# STM32F030F4P6.net
KiCad netlist of a schematic drawn in Altium Designer
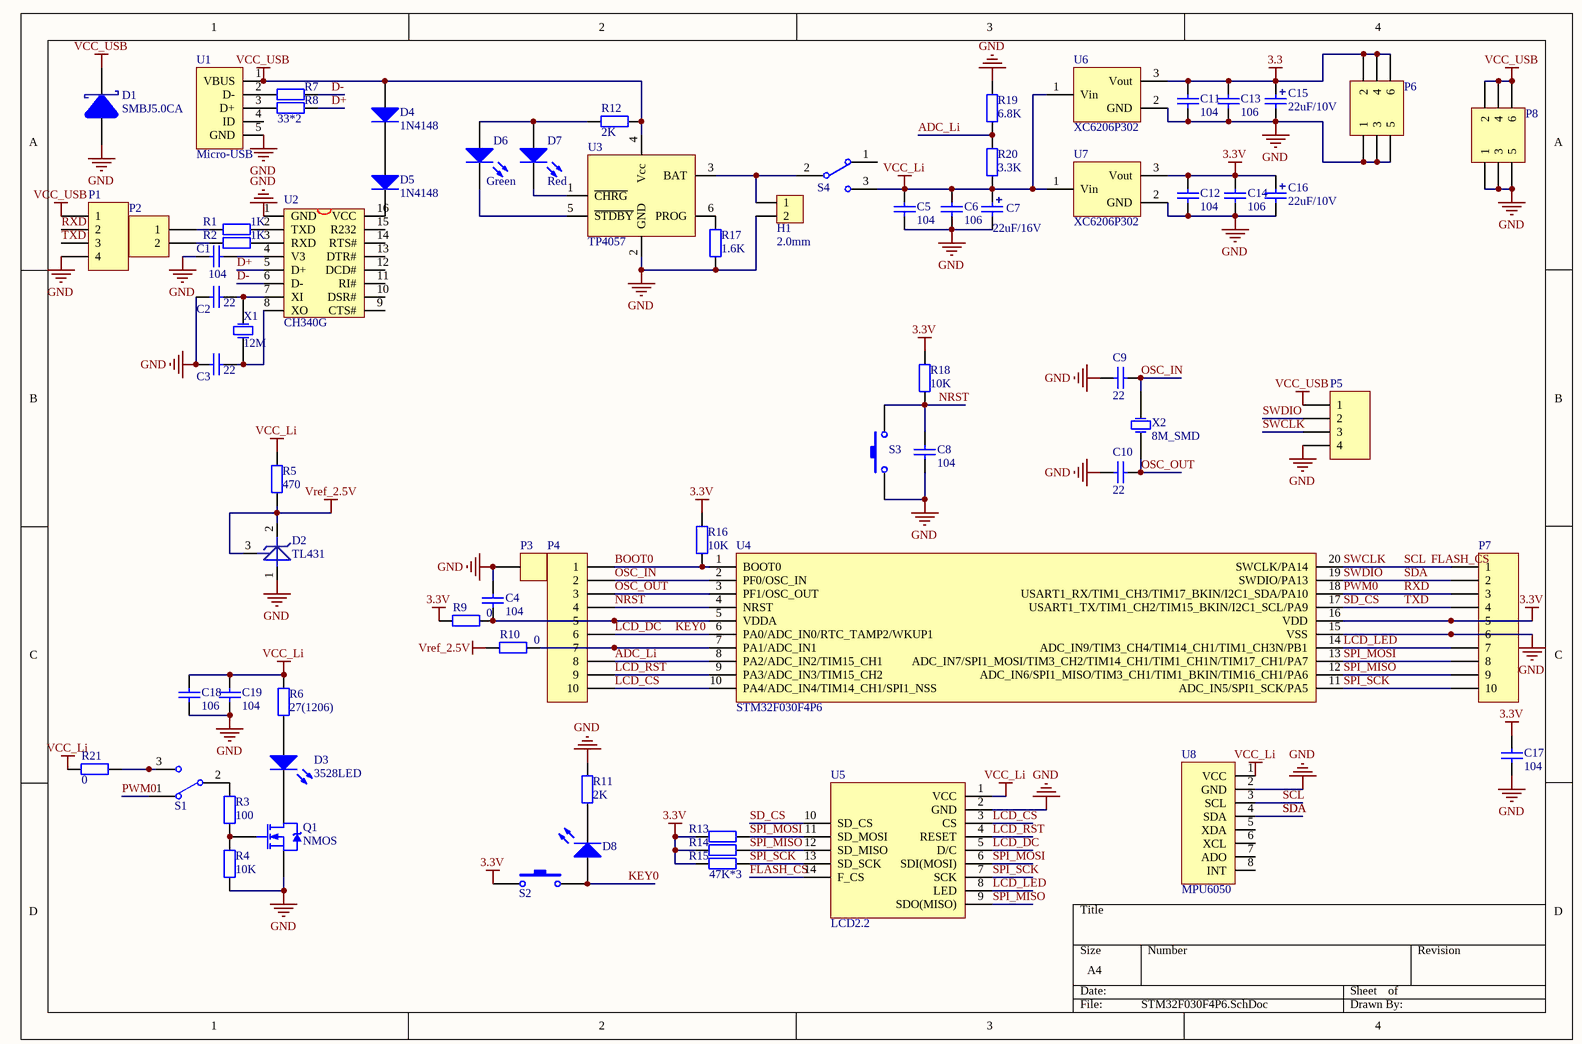
[diagram p0: STM32F030F4P6.SchDoc]

(export (version "E")
  (design (tool "Eeschema 10.0.6"))
  (components
    (comp (ref "C1")
      (value "104")
      (footprint "0603")
      (description "Capacitor")
      (fields (field (name "Comment") "Cap1") (field (name "PUBLISHER") "Altium Limited"))
      (libsource (lib "weifengdq") (part "Cap1"))
    )
    (comp (ref "C2")
      (value "22")
      (footprint "0603")
      (description "Capacitor")
      (fields (field (name "Comment") "Cap1") (field (name "PUBLISHER") "Altium Limited"))
      (libsource (lib "weifengdq") (part "Cap1"))
    )
    (comp (ref "C3")
      (value "22")
      (footprint "0603")
      (description "Capacitor")
      (fields (field (name "Comment") "Cap1") (field (name "PUBLISHER") "Altium Limited"))
      (libsource (lib "weifengdq") (part "Cap1"))
    )
    (comp (ref "C4")
      (value "104")
      (footprint "0603")
      (description "Capacitor")
      (fields (field (name "Comment") "Cap1") (field (name "PUBLISHER") "Altium Limited"))
      (libsource (lib "weifengdq") (part "Cap1"))
    )
    (comp (ref "C5")
      (value "104")
      (footprint "0603")
      (description "Capacitor")
      (fields (field (name "Comment") "Cap1") (field (name "PUBLISHER") "Altium Limited"))
      (libsource (lib "weifengdq") (part "Cap1"))
    )
    (comp (ref "C6")
      (value "106")
      (footprint "0603")
      (description "Capacitor")
      (fields (field (name "Comment") "Cap1") (field (name "PUBLISHER") "Altium Limited"))
      (libsource (lib "weifengdq") (part "Cap1"))
    )
    (comp (ref "C7")
      (value "22uF/16V")
      (footprint "3528(22u16V钽电容)")
      (description "Capacitor")
      (fields (field (name "Comment") "Cap_Pol") (field (name "PUBLISHER") "Altium Limited"))
      (libsource (lib "weifengdq") (part "Cap_Pol"))
    )
    (comp (ref "C8")
      (value "104")
      (footprint "0603")
      (description "Capacitor")
      (fields (field (name "Comment") "Cap1") (field (name "PUBLISHER") "Altium Limited"))
      (libsource (lib "weifengdq") (part "Cap1"))
    )
    (comp (ref "C9")
      (value "22")
      (footprint "0603")
      (description "Capacitor")
      (fields (field (name "Comment") "Cap1") (field (name "PUBLISHER") "Altium Limited"))
      (libsource (lib "weifengdq") (part "Cap1"))
    )
    (comp (ref "C10")
      (value "22")
      (footprint "0603")
      (description "Capacitor")
      (fields (field (name "Comment") "Cap1") (field (name "PUBLISHER") "Altium Limited"))
      (libsource (lib "weifengdq") (part "Cap1"))
    )
    (comp (ref "C11")
      (value "104")
      (footprint "0603")
      (description "Capacitor")
      (fields (field (name "Comment") "Cap1") (field (name "PUBLISHER") "Altium Limited"))
      (libsource (lib "weifengdq") (part "Cap1"))
    )
    (comp (ref "C12")
      (value "104")
      (footprint "0603")
      (description "Capacitor")
      (fields (field (name "Comment") "Cap1") (field (name "PUBLISHER") "Altium Limited"))
      (libsource (lib "weifengdq") (part "Cap1"))
    )
    (comp (ref "C13")
      (value "106")
      (footprint "0603")
      (description "Capacitor")
      (fields (field (name "Comment") "Cap1") (field (name "PUBLISHER") "Altium Limited"))
      (libsource (lib "weifengdq") (part "Cap1"))
    )
    (comp (ref "C14")
      (value "106")
      (footprint "0603")
      (description "Capacitor")
      (fields (field (name "Comment") "Cap1") (field (name "PUBLISHER") "Altium Limited"))
      (libsource (lib "weifengdq") (part "Cap1"))
    )
    (comp (ref "C15")
      (value "22uF/10V")
      (footprint "3216[1206]")
      (description "Capacitor")
      (fields (field (name "Comment") "Cap_Pol") (field (name "PUBLISHER") "Altium Limited"))
      (libsource (lib "weifengdq") (part "Cap_Pol"))
    )
    (comp (ref "C16")
      (value "22uF/10V")
      (footprint "3216[1206]")
      (description "Capacitor")
      (fields (field (name "Comment") "Cap_Pol") (field (name "PUBLISHER") "Altium Limited"))
      (libsource (lib "weifengdq") (part "Cap_Pol"))
    )
    (comp (ref "C17")
      (value "104")
      (footprint "0603")
      (description "Capacitor")
      (fields (field (name "Comment") "Cap1") (field (name "PUBLISHER") "Altium Limited"))
      (libsource (lib "weifengdq") (part "Cap1"))
    )
    (comp (ref "C18")
      (value "106")
      (footprint "0603")
      (description "Capacitor")
      (fields (field (name "Comment") "Cap1") (field (name "PUBLISHER") "Altium Limited"))
      (libsource (lib "weifengdq") (part "Cap1"))
    )
    (comp (ref "C19")
      (value "104")
      (footprint "0603")
      (description "Capacitor")
      (fields (field (name "Comment") "Cap1") (field (name "PUBLISHER") "Altium Limited"))
      (libsource (lib "weifengdq") (part "Cap1"))
    )
    (comp (ref "D1") (value "SMBJ5.0CA") (footprint "TVS") (libsource (lib "weifengdq") (part "TVS")))
    (comp (ref "D2") (value "TL431") (footprint "SOT-23") (libsource (lib "weifengdq") (part "TL431-SOT23")))
    (comp (ref "D3")
      (value "3528LED")
      (footprint "3528(22u16V钽电容)")
      (description "Typical INFRARED GaAs LED")
      (fields (field (name "PUBLISHER") "Altium Limited"))
      (libsource (lib "weifengdq") (part "LED1"))
    )
    (comp (ref "D4")
      (value "1N4148")
      (footprint "1N4148")
      (description "Default Diode")
      (fields (field (name "PUBLISHER") "Altium Limited"))
      (libsource (lib "weifengdq") (part "1N4148"))
    )
    (comp (ref "D5")
      (value "1N4148")
      (footprint "1N4148")
      (description "Default Diode")
      (fields (field (name "PUBLISHER") "Altium Limited"))
      (libsource (lib "weifengdq") (part "1N4148"))
    )
    (comp (ref "D6")
      (value "Green")
      (footprint "0603-Polar")
      (description "Typical INFRARED GaAs LED")
      (fields (field (name "PUBLISHER") "Altium Limited"))
      (libsource (lib "weifengdq") (part "LED1"))
    )
    (comp (ref "D7")
      (value "Red")
      (footprint "0603-Polar")
      (description "Typical INFRARED GaAs LED")
      (fields (field (name "PUBLISHER") "Altium Limited"))
      (libsource (lib "weifengdq") (part "LED1"))
    )
    (comp (ref "D8")
      (value "LED1")
      (footprint "0603-Polar")
      (description "Typical INFRARED GaAs LED")
      (fields (field (name "PUBLISHER") "Altium Limited"))
      (libsource (lib "weifengdq") (part "LED1"))
    )
    (comp (ref "H1") (value "2.0mm") (footprint "H2-防反 2.0") (libsource (lib "weifengdq") (part "H2-防反")))
    (comp (ref "P1")
      (value "Header 4")
      (footprint "HDR1X4")
      (description "Header, 4-Pin")
      (fields (field (name "PUBLISHER") "Altium Limited"))
      (libsource (lib "Miscellaneous Connectors") (part "Header 4"))
    )
    (comp (ref "P2")
      (value "Header 2")
      (footprint "HDR1X2")
      (description "Header, 2-Pin")
      (fields (field (name "PUBLISHER") "Altium Limited"))
      (libsource (lib "Miscellaneous Connectors") (part "Header 2"))
    )
    (comp (ref "P3") (value "TEST") (footprint "HDR1X1") (libsource (lib "weifengdq") (part "TEST")))
    (comp (ref "P4")
      (value "Header 10")
      (footprint "HDR1X10")
      (description "Header, 10-Pin")
      (fields (field (name "PUBLISHER") "Altium Limited"))
      (libsource (lib "") (part "Header 10_1"))
    )
    (comp (ref "P5")
      (value "Header 4")
      (footprint "HDR1X4")
      (description "Header, 4-Pin")
      (fields (field (name "PUBLISHER") "Altium Limited"))
      (libsource (lib "Miscellaneous Connectors") (part "Header 4"))
    )
    (comp (ref "P6")
      (value "Header 3X2")
      (footprint "HDR2X3")
      (description "Header, 3-Pin, Dual row")
      (fields (field (name "PUBLISHER") "Altium Limited"))
      (libsource (lib "Miscellaneous Connectors") (part "Header 3X2"))
    )
    (comp (ref "P7")
      (value "Header 10")
      (footprint "HDR1X10")
      (description "Header, 10-Pin")
      (fields (field (name "PUBLISHER") "Altium Limited"))
      (libsource (lib "Miscellaneous Connectors") (part "Header 10"))
    )
    (comp (ref "P8")
      (value "Header 3X2")
      (footprint "HDR2X3")
      (description "Header, 3-Pin, Dual row")
      (fields (field (name "PUBLISHER") "Altium Limited"))
      (libsource (lib "Miscellaneous Connectors") (part "Header 3X2"))
    )
    (comp (ref "Q1")
      (value "NMOS")
      (footprint "SOT-23-3 - AO3400")
      (description "N-Channel Power MOSFET")
      (fields (field (name "PUBLISHER") "Altium Limited"))
      (libsource (lib "weifengdq") (part "NMOS"))
    )
    (comp (ref "R1")
      (value "1K")
      (footprint "0603")
      (description "Resistor")
      (fields (field (name "Comment") "Res1") (field (name "PUBLISHER") "Altium Limited"))
      (libsource (lib "") (part "Res1_2"))
    )
    (comp (ref "R2")
      (value "1K")
      (footprint "0603")
      (description "Resistor")
      (fields (field (name "Comment") "Res1") (field (name "PUBLISHER") "Altium Limited"))
      (libsource (lib "") (part "Res1_2"))
    )
    (comp (ref "R3")
      (value "100")
      (footprint "0603")
      (description "Resistor")
      (fields (field (name "Comment") "Res1") (field (name "PUBLISHER") "Altium Limited"))
      (libsource (lib "") (part "Res1_1"))
    )
    (comp (ref "R4")
      (value "10K")
      (footprint "0603")
      (description "Resistor")
      (fields (field (name "Comment") "Res1") (field (name "PUBLISHER") "Altium Limited"))
      (libsource (lib "") (part "Res1_1"))
    )
    (comp (ref "R5")
      (value "470")
      (footprint "0603")
      (description "Resistor")
      (fields (field (name "Comment") "Res1") (field (name "PUBLISHER") "Altium Limited"))
      (libsource (lib "") (part "Res1_1"))
    )
    (comp (ref "R6")
      (value "27(1206)")
      (footprint "3216[1206]")
      (description "Resistor")
      (fields (field (name "Comment") "Res1") (field (name "PUBLISHER") "Altium Limited"))
      (libsource (lib "") (part "Res1_1"))
    )
    (comp (ref "R7")
      (value "Res1")
      (footprint "0603")
      (description "Resistor")
      (fields (field (name "PUBLISHER") "Altium Limited"))
      (libsource (lib "") (part "Res1_2"))
    )
    (comp (ref "R8")
      (value "33*2")
      (footprint "0603")
      (description "Resistor")
      (fields (field (name "Comment") "Res1") (field (name "PUBLISHER") "Altium Limited"))
      (libsource (lib "") (part "Res1_2"))
    )
    (comp (ref "R9")
      (value "0")
      (footprint "0603")
      (description "Resistor")
      (fields (field (name "Comment") "Res1") (field (name "PUBLISHER") "Altium Limited"))
      (libsource (lib "") (part "Res1_2"))
    )
    (comp (ref "R10")
      (value "0")
      (footprint "0603")
      (description "Resistor")
      (fields (field (name "Comment") "Res1") (field (name "PUBLISHER") "Altium Limited"))
      (libsource (lib "") (part "Res1_2"))
    )
    (comp (ref "R11")
      (value "2K")
      (footprint "0603")
      (description "Resistor")
      (fields (field (name "Comment") "Res1") (field (name "PUBLISHER") "Altium Limited"))
      (libsource (lib "") (part "Res1_1"))
    )
    (comp (ref "R12")
      (value "2K")
      (footprint "0603")
      (description "Resistor")
      (fields (field (name "Comment") "Res1") (field (name "PUBLISHER") "Altium Limited"))
      (libsource (lib "weifengdq") (part "Res1"))
    )
    (comp (ref "R13")
      (value "Res1")
      (footprint "0603")
      (description "Resistor")
      (fields (field (name "PUBLISHER") "Altium Limited"))
      (libsource (lib "weifengdq") (part "Res1"))
    )
    (comp (ref "R14")
      (value "Res1")
      (footprint "0603")
      (description "Resistor")
      (fields (field (name "PUBLISHER") "Altium Limited"))
      (libsource (lib "weifengdq") (part "Res1"))
    )
    (comp (ref "R15")
      (value "47K*3")
      (footprint "0603")
      (description "Resistor")
      (fields (field (name "Comment") "Res1") (field (name "PUBLISHER") "Altium Limited"))
      (libsource (lib "weifengdq") (part "Res1"))
    )
    (comp (ref "R16")
      (value "10K")
      (footprint "0603")
      (description "Resistor")
      (fields (field (name "Comment") "Res1") (field (name "PUBLISHER") "Altium Limited"))
      (libsource (lib "") (part "Res1_1"))
    )
    (comp (ref "R17")
      (value "1.6K")
      (footprint "0603")
      (description "Resistor")
      (fields (field (name "Comment") "Res1") (field (name "PUBLISHER") "Altium Limited"))
      (libsource (lib "") (part "Res1_1"))
    )
    (comp (ref "R18")
      (value "10K")
      (footprint "0603")
      (description "Resistor")
      (fields (field (name "Comment") "Res1") (field (name "PUBLISHER") "Altium Limited"))
      (libsource (lib "") (part "Res1_1"))
    )
    (comp (ref "R19")
      (value "6.8K")
      (footprint "0603")
      (description "Resistor")
      (fields (field (name "Comment") "Res1") (field (name "PUBLISHER") "Altium Limited"))
      (libsource (lib "") (part "Res1_1"))
    )
    (comp (ref "R20")
      (value "3.3K")
      (footprint "0603")
      (description "Resistor")
      (fields (field (name "Comment") "Res1") (field (name "PUBLISHER") "Altium Limited"))
      (libsource (lib "") (part "Res1_1"))
    )
    (comp (ref "R21")
      (value "0")
      (footprint "0603")
      (description "Resistor")
      (fields (field (name "Comment") "Res1") (field (name "PUBLISHER") "Altium Limited"))
      (libsource (lib "") (part "Res1_2"))
    )
    (comp (ref "S1")
      (value "SW3")
      (footprint "SW-3")
      (description "Switch")
      (fields (field (name "PUBLISHER") "Altium Limited"))
      (libsource (lib "weifengdq") (part "SW3"))
    )
    (comp (ref "S2")
      (value "SW-PB_1")
      (footprint "SW-2")
      (description "Switch")
      (fields (field (name "PUBLISHER") "Altium Limited"))
      (libsource (lib "weifengdq") (part "SW-PB_1"))
    )
    (comp (ref "S3")
      (value "SW-PB_1")
      (footprint "SW-2")
      (description "Switch")
      (fields (field (name "PUBLISHER") "Altium Limited"))
      (libsource (lib "weifengdq") (part "SW-PB_1"))
    )
    (comp (ref "S4")
      (value "SW3")
      (footprint "SW-3")
      (description "Switch")
      (fields (field (name "PUBLISHER") "Altium Limited"))
      (libsource (lib "weifengdq") (part "SW3"))
    )
    (comp (ref "U1")
      (value "Micro-USB")
      (footprint "MICRO-USB-F")
      (libsource (lib "weifengdq") (part "Micro-USB"))
    )
    (comp (ref "U2")
      (value "CH340G")
      (footprint "SOP16M")
      (description "USB2UART")
      (libsource (lib "weifengdq") (part "CH340G"))
    )
    (comp (ref "U3") (value "TP4057") (footprint "SOT-23-6") (libsource (lib "weifengdq") (part "TP4057")))
    (comp (ref "U4")
      (value "STM32F030F4P6")
      (footprint "TSSOP20")
      (libsource (lib "weifengdq") (part "STM32F030F4P6"))
    )
    (comp (ref "U5") (value "LCD2.2") (footprint "LCD2.2 _2") (libsource (lib "weifengdq") (part "LCD2.2")))
    (comp (ref "U6") (value "XC6206P302") (footprint "SOT-23") (libsource (lib "weifengdq") (part "662k")))
    (comp (ref "U7") (value "XC6206P302") (footprint "SOT-23") (libsource (lib "weifengdq") (part "662k")))
    (comp (ref "U8") (value "MPU6050") (footprint "HDR1X8") (libsource (lib "weifengdq") (part "MPU6050_1")))
    (comp (ref "X1")
      (value "12M")
      (footprint "XTAL_SMD")
      (description "Crystal Oscillator")
      (fields (field (name "PUBLISHER") "Altium Limited"))
      (libsource (lib "weifengdq") (part "XTAL_1"))
    )
    (comp (ref "X2")
      (value "8M_SMD")
      (footprint "XTAL_SMD")
      (description "Crystal Oscillator")
      (fields (field (name "PUBLISHER") "Altium Limited"))
      (libsource (lib "weifengdq") (part "XTAL_1"))
    )
  )
  (nets
    (net (code "1") (name "/ADC_Li") (class "Default")
      (node (ref "P4") (pin "8") (pinfunction "8_8") (pintype "passive"))
      (node (ref "R19") (pin "1") (pinfunction "1_1") (pintype "passive"))
      (node (ref "R20") (pin "2") (pinfunction "2_2") (pintype "passive"))
      (node (ref "U4") (pin "8") (pinfunction "PA2/ADC_IN2/TIM15_CH1_8") (pintype "passive"))
    )
    (net (code "2") (name "/BOOT0") (class "Default")
      (node (ref "P4") (pin "1") (pinfunction "1_1") (pintype "passive"))
      (node (ref "R16") (pin "1") (pinfunction "1_1") (pintype "passive"))
      (node (ref "U4") (pin "1") (pinfunction "BOOT0_1") (pintype "passive"))
    )
    (net (code "3") (name "/D+") (class "Default")
      (node (ref "R8") (pin "2") (pinfunction "2_2") (pintype "passive"))
      (node (ref "U2") (pin "5") (pinfunction "D+_5") (pintype "passive"))
    )
    (net (code "4") (name "/D-") (class "Default")
      (node (ref "R7") (pin "2") (pinfunction "2_2") (pintype "passive"))
      (node (ref "U2") (pin "6") (pinfunction "D-_6") (pintype "passive"))
    )
    (net (code "5") (name "/FLASH_CS") (class "Default")
      (node (ref "P5") (pin "3") (pinfunction "3_3") (pintype "passive"))
      (node (ref "P7") (pin "1") (pinfunction "1_1") (pintype "passive"))
      (node (ref "U4") (pin "20") (pinfunction "SWCLK/PA14_20") (pintype "passive"))
      (node (ref "U5") (pin "14") (pinfunction "F_CS_14") (pintype "passive"))
      (node (ref "U8") (pin "3") (pinfunction "SCL_3") (pintype "passive"))
    )
    (net (code "6") (name "/KEY0") (class "Default")
      (node (ref "D8") (pin "1") (pinfunction "A_1") (pintype "passive"))
      (node (ref "P4") (pin "6") (pinfunction "6_6") (pintype "passive"))
      (node (ref "S2") (pin "2") (pinfunction "2_2") (pintype "passive"))
      (node (ref "U4") (pin "6") (pinfunction "PA0/ADC_IN0/RTC_TAMP2/WKUP1_6") (pintype "passive"))
      (node (ref "U5") (pin "5") (pinfunction "D/C_5") (pintype "passive"))
    )
    (net (code "7") (name "/LCD_CS") (class "Default")
      (node (ref "P4") (pin "10") (pinfunction "10_10") (pintype "passive"))
      (node (ref "U4") (pin "10") (pinfunction "PA4/ADC_IN4/TIM14_CH1/SPI1_NSS_10") (pintype "passive"))
      (node (ref "U5") (pin "3") (pinfunction "CS_3") (pintype "passive"))
    )
    (net (code "8") (name "/LCD_LED") (class "Default")
      (node (ref "P7") (pin "7") (pinfunction "7_7") (pintype "passive"))
      (node (ref "U4") (pin "14") (pinfunction "ADC_IN9/TIM3_CH4/TIM14_CH1/TIM1_CH3N/PB1_14") (pintype "passive"))
      (node (ref "U5") (pin "8") (pinfunction "LED_8") (pintype "passive"))
    )
    (net (code "9") (name "/LCD_RST") (class "Default")
      (node (ref "P4") (pin "9") (pinfunction "9_9") (pintype "passive"))
      (node (ref "U4") (pin "9") (pinfunction "PA3/ADC_IN3/TIM15_CH2_9") (pintype "passive"))
      (node (ref "U5") (pin "4") (pinfunction "RESET_4") (pintype "passive"))
    )
    (net (code "10") (name "/NRST") (class "Default")
      (node (ref "C8") (pin "2") (pinfunction "2_2") (pintype "passive"))
      (node (ref "P4") (pin "4") (pinfunction "4_4") (pintype "passive"))
      (node (ref "R18") (pin "1") (pinfunction "1_1") (pintype "passive"))
      (node (ref "S3") (pin "2") (pinfunction "2_2") (pintype "passive"))
      (node (ref "U4") (pin "4") (pinfunction "NRST_4") (pintype "passive"))
    )
    (net (code "11") (name "/OSC_IN") (class "Default")
      (node (ref "C9") (pin "2") (pinfunction "2_2") (pintype "passive"))
      (node (ref "P4") (pin "2") (pinfunction "2_2") (pintype "passive"))
      (node (ref "U4") (pin "2") (pinfunction "PF0/OSC_IN_2") (pintype "passive"))
      (node (ref "X2") (pin "2") (pinfunction "OSC2_2") (pintype "passive"))
    )
    (net (code "12") (name "/OSC_OUT") (class "Default")
      (node (ref "C10") (pin "2") (pinfunction "2_2") (pintype "passive"))
      (node (ref "P4") (pin "3") (pinfunction "3_3") (pintype "passive"))
      (node (ref "U4") (pin "3") (pinfunction "PF1/OSC_OUT_3") (pintype "passive"))
      (node (ref "X2") (pin "1") (pinfunction "OSC1_1") (pintype "passive"))
    )
    (net (code "13") (name "/PWM0") (class "Default")
      (node (ref "P1") (pin "2") (pinfunction "2_2") (pintype "passive"))
      (node (ref "P7") (pin "3") (pinfunction "3_3") (pintype "passive"))
      (node (ref "S1") (pin "1") (pinfunction "1_1") (pintype "passive"))
      (node (ref "U4") (pin "18") (pinfunction "USART1_RX/TIM1_CH3/TIM17_BKIN/I2C1_SDA/PA10_18") (pintype "passive"))
    )
    (net (code "14") (name "/SDA") (class "Default")
      (node (ref "P5") (pin "2") (pinfunction "2_2") (pintype "passive"))
      (node (ref "P7") (pin "2") (pinfunction "2_2") (pintype "passive"))
      (node (ref "U4") (pin "19") (pinfunction "SWDIO/PA13_19") (pintype "passive"))
      (node (ref "U8") (pin "4") (pinfunction "SDA_4") (pintype "passive"))
    )
    (net (code "15") (name "/SD_CS") (class "Default")
      (node (ref "P1") (pin "3") (pinfunction "3_3") (pintype "passive"))
      (node (ref "P7") (pin "4") (pinfunction "4_4") (pintype "passive"))
      (node (ref "U4") (pin "17") (pinfunction "USART1_TX/TIM1_CH2/TIM15_BKIN/I2C1_SCL/PA9_17") (pintype "passive"))
      (node (ref "U5") (pin "10") (pinfunction "SD_CS_10") (pintype "passive"))
    )
    (net (code "16") (name "/SPI_MISO") (class "Default")
      (node (ref "P7") (pin "9") (pinfunction "9_9") (pintype "passive"))
      (node (ref "R14") (pin "1") (pinfunction "1_1") (pintype "passive"))
      (node (ref "U4") (pin "12") (pinfunction "ADC_IN6/SPI1_MISO/TIM3_CH1/TIM1_BKIN/TIM16_CH1/PA6_12") (pintype "passive"))
      (node (ref "U5") (pin "12") (pinfunction "SD_MISO_12") (pintype "passive"))
      (node (ref "U5") (pin "9") (pinfunction "SDO(MISO)_9") (pintype "passive"))
    )
    (net (code "17") (name "/SPI_MOSI") (class "Default")
      (node (ref "P7") (pin "8") (pinfunction "8_8") (pintype "passive"))
      (node (ref "R13") (pin "1") (pinfunction "1_1") (pintype "passive"))
      (node (ref "U4") (pin "13") (pinfunction "ADC_IN7/SPI1_MOSI/TIM3_CH2/TIM14_CH1/TIM1_CH1N/TIM17_CH1/PA7_13") (pintype "passive"))
      (node (ref "U5") (pin "11") (pinfunction "SD_MOSI_11") (pintype "passive"))
      (node (ref "U5") (pin "6") (pinfunction "SDI(MOSI)_6") (pintype "passive"))
    )
    (net (code "18") (name "/SPI_SCK") (class "Default")
      (node (ref "P7") (pin "10") (pinfunction "10_10") (pintype "passive"))
      (node (ref "R15") (pin "1") (pinfunction "1_1") (pintype "passive"))
      (node (ref "U4") (pin "11") (pinfunction "ADC_IN5/SPI1_SCK/PA5_11") (pintype "passive"))
      (node (ref "U5") (pin "13") (pinfunction "SD_SCK_13") (pintype "passive"))
      (node (ref "U5") (pin "7") (pinfunction "SCK_7") (pintype "passive"))
    )
    (net (code "19") (name "3.3") (class "Default")
      (node (ref "C11") (pin "2") (pinfunction "2_2") (pintype "passive"))
      (node (ref "C13") (pin "2") (pinfunction "2_2") (pintype "passive"))
      (node (ref "C15") (pin "1") (pinfunction "1_1") (pintype "passive"))
      (node (ref "P6") (pin "2") (pinfunction "2_2") (pintype "passive"))
      (node (ref "P6") (pin "4") (pinfunction "4_4") (pintype "passive"))
      (node (ref "P6") (pin "6") (pinfunction "6_6") (pintype "passive"))
      (node (ref "U6") (pin "3") (pinfunction "Vout_3") (pintype "passive"))
    )
    (net (code "20") (name "3.3V") (class "Default")
      (node (ref "C12") (pin "2") (pinfunction "2_2") (pintype "passive"))
      (node (ref "C14") (pin "2") (pinfunction "2_2") (pintype "passive"))
      (node (ref "C16") (pin "1") (pinfunction "1_1") (pintype "passive"))
      (node (ref "C17") (pin "2") (pinfunction "2_2") (pintype "passive"))
      (node (ref "P7") (pin "5") (pinfunction "5_5") (pintype "passive"))
      (node (ref "R13") (pin "2") (pinfunction "2_2") (pintype "passive"))
      (node (ref "R14") (pin "2") (pinfunction "2_2") (pintype "passive"))
      (node (ref "R15") (pin "2") (pinfunction "2_2") (pintype "passive"))
      (node (ref "R16") (pin "2") (pinfunction "2_2") (pintype "passive"))
      (node (ref "R18") (pin "2") (pinfunction "2_2") (pintype "passive"))
      (node (ref "R9") (pin "1") (pinfunction "1_1") (pintype "passive"))
      (node (ref "S2") (pin "1") (pinfunction "1_1") (pintype "passive"))
      (node (ref "U4") (pin "16") (pinfunction "VDD_16") (pintype "passive"))
      (node (ref "U7") (pin "3") (pinfunction "Vout_3") (pintype "passive"))
    )
    (net (code "21") (name "GND") (class "Default")
      (node (ref "C1") (pin "1") (pinfunction "1_1") (pintype "passive"))
      (node (ref "C10") (pin "1") (pinfunction "1_1") (pintype "passive"))
      (node (ref "C11") (pin "1") (pinfunction "1_1") (pintype "passive"))
      (node (ref "C12") (pin "1") (pinfunction "1_1") (pintype "passive"))
      (node (ref "C13") (pin "1") (pinfunction "1_1") (pintype "passive"))
      (node (ref "C14") (pin "1") (pinfunction "1_1") (pintype "passive"))
      (node (ref "C15") (pin "2") (pinfunction "2_2") (pintype "passive"))
      (node (ref "C16") (pin "2") (pinfunction "2_2") (pintype "passive"))
      (node (ref "C17") (pin "1") (pinfunction "1_1") (pintype "passive"))
      (node (ref "C18") (pin "1") (pinfunction "1_1") (pintype "passive"))
      (node (ref "C19") (pin "1") (pinfunction "1_1") (pintype "passive"))
      (node (ref "C2") (pin "1") (pinfunction "1_1") (pintype "passive"))
      (node (ref "C3") (pin "1") (pinfunction "1_1") (pintype "passive"))
      (node (ref "C4") (pin "2") (pinfunction "2_2") (pintype "passive"))
      (node (ref "C5") (pin "1") (pinfunction "1_1") (pintype "passive"))
      (node (ref "C6") (pin "1") (pinfunction "1_1") (pintype "passive"))
      (node (ref "C7") (pin "2") (pinfunction "2_2") (pintype "passive"))
      (node (ref "C8") (pin "1") (pinfunction "1_1") (pintype "passive"))
      (node (ref "C9") (pin "1") (pinfunction "1_1") (pintype "passive"))
      (node (ref "D1") (pin "1") (pinfunction "1_1") (pintype "passive"))
      (node (ref "D2") (pin "1") (pinfunction "1_1") (pintype "passive"))
      (node (ref "H1") (pin "2") (pinfunction "2_2") (pintype "passive"))
      (node (ref "P1") (pin "4") (pinfunction "4_4") (pintype "passive"))
      (node (ref "P3") (pin "1") (pinfunction "1_1") (pintype "passive"))
      (node (ref "P5") (pin "4") (pinfunction "4_4") (pintype "passive"))
      (node (ref "P6") (pin "1") (pinfunction "1_1") (pintype "passive"))
      (node (ref "P6") (pin "3") (pinfunction "3_3") (pintype "passive"))
      (node (ref "P6") (pin "5") (pinfunction "5_5") (pintype "passive"))
      (node (ref "P7") (pin "6") (pinfunction "6_6") (pintype "passive"))
      (node (ref "P8") (pin "1") (pinfunction "1_1") (pintype "passive"))
      (node (ref "P8") (pin "3") (pinfunction "3_3") (pintype "passive"))
      (node (ref "P8") (pin "5") (pinfunction "5_5") (pintype "passive"))
      (node (ref "Q1") (pin "3") (pinfunction "S_3") (pintype "passive"))
      (node (ref "R11") (pin "2") (pinfunction "2_2") (pintype "passive"))
      (node (ref "R17") (pin "1") (pinfunction "1_1") (pintype "passive"))
      (node (ref "R19") (pin "2") (pinfunction "2_2") (pintype "passive"))
      (node (ref "R4") (pin "1") (pinfunction "1_1") (pintype "passive"))
      (node (ref "S3") (pin "1") (pinfunction "1_1") (pintype "passive"))
      (node (ref "U1") (pin "5") (pinfunction "GND_5") (pintype "passive"))
      (node (ref "U2") (pin "1") (pinfunction "GND_1") (pintype "passive"))
      (node (ref "U3") (pin "2") (pinfunction "GND_2") (pintype "passive"))
      (node (ref "U4") (pin "15") (pinfunction "VSS_15") (pintype "passive"))
      (node (ref "U5") (pin "2") (pinfunction "GND_2") (pintype "passive"))
      (node (ref "U6") (pin "2") (pinfunction "GND_2") (pintype "passive"))
      (node (ref "U7") (pin "2") (pinfunction "GND_2") (pintype "passive"))
      (node (ref "U8") (pin "2") (pinfunction "GND_2") (pintype "passive"))
    )
    (net (code "22") (name "Net-(D3-A)") (class "Default")
      (node (ref "D3") (pin "1") (pinfunction "A_1") (pintype "passive"))
      (node (ref "R6") (pin "1") (pinfunction "1_1") (pintype "passive"))
    )
    (net (code "23") (name "Net-(D3-K)") (class "Default")
      (node (ref "D3") (pin "2") (pinfunction "K_2") (pintype "passive"))
      (node (ref "Q1") (pin "2") (pinfunction "D_2") (pintype "passive"))
    )
    (net (code "24") (name "Net-(D4-K)") (class "Default")
      (node (ref "D4") (pin "2") (pinfunction "K_2") (pintype "passive"))
      (node (ref "D5") (pin "1") (pinfunction "A_1") (pintype "passive"))
    )
    (net (code "25") (name "Net-(D5-K)") (class "Default")
      (node (ref "D5") (pin "2") (pinfunction "K_2") (pintype "passive"))
      (node (ref "U2") (pin "16") (pinfunction "VCC_16") (pintype "passive"))
    )
    (net (code "26") (name "Net-(D6-A)") (class "Default")
      (node (ref "D6") (pin "1") (pinfunction "A_1") (pintype "passive"))
      (node (ref "D7") (pin "1") (pinfunction "A_1") (pintype "passive"))
      (node (ref "R12") (pin "2") (pinfunction "2_2") (pintype "passive"))
    )
    (net (code "27") (name "Net-(D6-K)") (class "Default")
      (node (ref "D6") (pin "2") (pinfunction "K_2") (pintype "passive"))
      (node (ref "U3") (pin "5") (pinfunction "~{STDBY}_5") (pintype "passive"))
    )
    (net (code "28") (name "Net-(D7-K)") (class "Default")
      (node (ref "D7") (pin "2") (pinfunction "K_2") (pintype "passive"))
      (node (ref "U3") (pin "1") (pinfunction "~{CHRG}_1") (pintype "passive"))
    )
    (net (code "29") (name "Net-(D8-K)") (class "Default")
      (node (ref "D8") (pin "2") (pinfunction "K_2") (pintype "passive"))
      (node (ref "R11") (pin "1") (pinfunction "1_1") (pintype "passive"))
    )
    (net (code "30") (name "Net-(P2-Pad1)") (class "Default")
      (node (ref "P2") (pin "1") (pinfunction "1_1") (pintype "passive"))
      (node (ref "R1") (pin "1") (pinfunction "1_1") (pintype "passive"))
    )
    (net (code "31") (name "Net-(P2-Pad2)") (class "Default")
      (node (ref "P2") (pin "2") (pinfunction "2_2") (pintype "passive"))
      (node (ref "R2") (pin "1") (pinfunction "1_1") (pintype "passive"))
    )
    (net (code "32") (name "Net-(Q1-G)") (class "Default")
      (node (ref "Q1") (pin "1") (pinfunction "G_1") (pintype "passive"))
      (node (ref "R3") (pin "1") (pinfunction "1_1") (pintype "passive"))
      (node (ref "R4") (pin "2") (pinfunction "2_2") (pintype "passive"))
    )
    (net (code "33") (name "Net-(R3-Pad2)") (class "Default")
      (node (ref "R3") (pin "2") (pinfunction "2_2") (pintype "passive"))
      (node (ref "S1") (pin "2") (pinfunction "2_2") (pintype "passive"))
    )
    (net (code "34") (name "Net-(R21-Pad2)") (class "Default")
      (node (ref "R21") (pin "2") (pinfunction "2_2") (pintype "passive"))
      (node (ref "S1") (pin "3") (pinfunction "3_3") (pintype "passive"))
    )
    (net (code "35") (name "Net-(U1-D+)") (class "Default")
      (node (ref "R8") (pin "1") (pinfunction "1_1") (pintype "passive"))
      (node (ref "U1") (pin "3") (pinfunction "D+_3") (pintype "passive"))
    )
    (net (code "36") (name "Net-(U1-D-)") (class "Default")
      (node (ref "R7") (pin "1") (pinfunction "1_1") (pintype "passive"))
      (node (ref "U1") (pin "2") (pinfunction "D-_2") (pintype "passive"))
    )
    (net (code "37") (name "Net-(U2-RXD)") (class "Default")
      (node (ref "R2") (pin "2") (pinfunction "2_2") (pintype "passive"))
      (node (ref "U2") (pin "3") (pinfunction "RXD_3") (pintype "passive"))
    )
    (net (code "38") (name "Net-(U2-TXD)") (class "Default")
      (node (ref "R1") (pin "2") (pinfunction "2_2") (pintype "passive"))
      (node (ref "U2") (pin "2") (pinfunction "TXD_2") (pintype "passive"))
    )
    (net (code "39") (name "Net-(U2-V3)") (class "Default")
      (node (ref "C1") (pin "2") (pinfunction "2_2") (pintype "passive"))
      (node (ref "U2") (pin "4") (pinfunction "V3_4") (pintype "passive"))
    )
    (net (code "40") (name "Net-(U2-XI)") (class "Default")
      (node (ref "C2") (pin "2") (pinfunction "2_2") (pintype "passive"))
      (node (ref "U2") (pin "7") (pinfunction "XI_7") (pintype "passive"))
      (node (ref "X1") (pin "2") (pinfunction "OSC2_2") (pintype "passive"))
    )
    (net (code "41") (name "Net-(U2-XO)") (class "Default")
      (node (ref "C3") (pin "2") (pinfunction "2_2") (pintype "passive"))
      (node (ref "U2") (pin "8") (pinfunction "XO_8") (pintype "passive"))
      (node (ref "X1") (pin "1") (pinfunction "OSC1_1") (pintype "passive"))
    )
    (net (code "42") (name "Net-(U3-BAT)") (class "Default")
      (node (ref "H1") (pin "1") (pinfunction "1_1") (pintype "passive"))
      (node (ref "S4") (pin "2") (pinfunction "2_2") (pintype "passive"))
      (node (ref "U3") (pin "3") (pinfunction "BAT_3") (pintype "passive"))
    )
    (net (code "43") (name "Net-(U3-PROG)") (class "Default")
      (node (ref "R17") (pin "2") (pinfunction "2_2") (pintype "passive"))
      (node (ref "U3") (pin "6") (pinfunction "PROG_6") (pintype "passive"))
    )
    (net (code "44") (name "Net-(U4-PA1{slash}ADC_IN1)") (class "Default")
      (node (ref "P4") (pin "7") (pinfunction "7_7") (pintype "passive"))
      (node (ref "R10") (pin "2") (pinfunction "2_2") (pintype "passive"))
      (node (ref "U4") (pin "7") (pinfunction "PA1/ADC_IN1_7") (pintype "passive"))
    )
    (net (code "45") (name "Net-(U4-VDDA)") (class "Default")
      (node (ref "C4") (pin "1") (pinfunction "1_1") (pintype "passive"))
      (node (ref "P4") (pin "5") (pinfunction "5_5") (pintype "passive"))
      (node (ref "R9") (pin "2") (pinfunction "2_2") (pintype "passive"))
      (node (ref "U4") (pin "5") (pinfunction "VDDA_5") (pintype "passive"))
    )
    (net (code "46") (name "VCC_Li") (class "Default")
      (node (ref "C18") (pin "2") (pinfunction "2_2") (pintype "passive"))
      (node (ref "C19") (pin "2") (pinfunction "2_2") (pintype "passive"))
      (node (ref "C5") (pin "2") (pinfunction "2_2") (pintype "passive"))
      (node (ref "C6") (pin "2") (pinfunction "2_2") (pintype "passive"))
      (node (ref "C7") (pin "1") (pinfunction "1_1") (pintype "passive"))
      (node (ref "R20") (pin "1") (pinfunction "1_1") (pintype "passive"))
      (node (ref "R21") (pin "1") (pinfunction "1_1") (pintype "passive"))
      (node (ref "R5") (pin "2") (pinfunction "2_2") (pintype "passive"))
      (node (ref "R6") (pin "2") (pinfunction "2_2") (pintype "passive"))
      (node (ref "S4") (pin "3") (pinfunction "3_3") (pintype "passive"))
      (node (ref "U5") (pin "1") (pinfunction "VCC_1") (pintype "passive"))
      (node (ref "U6") (pin "1") (pinfunction "Vin_1") (pintype "passive"))
      (node (ref "U7") (pin "1") (pinfunction "Vin_1") (pintype "passive"))
      (node (ref "U8") (pin "1") (pinfunction "VCC_1") (pintype "passive"))
    )
    (net (code "47") (name "VCC_USB") (class "Default")
      (node (ref "D1") (pin "2") (pinfunction "2_2") (pintype "passive"))
      (node (ref "D4") (pin "1") (pinfunction "A_1") (pintype "passive"))
      (node (ref "P1") (pin "1") (pinfunction "1_1") (pintype "passive"))
      (node (ref "P5") (pin "1") (pinfunction "1_1") (pintype "passive"))
      (node (ref "P8") (pin "2") (pinfunction "2_2") (pintype "passive"))
      (node (ref "P8") (pin "4") (pinfunction "4_4") (pintype "passive"))
      (node (ref "P8") (pin "6") (pinfunction "6_6") (pintype "passive"))
      (node (ref "R12") (pin "1") (pinfunction "1_1") (pintype "passive"))
      (node (ref "U1") (pin "1") (pinfunction "VBUS_1") (pintype "passive"))
      (node (ref "U3") (pin "4") (pinfunction "Vcc_4") (pintype "passive"))
    )
    (net (code "48") (name "Vref_2.5V") (class "Default")
      (node (ref "D2") (pin "2") (pinfunction "2_2") (pintype "passive"))
      (node (ref "D2") (pin "3") (pinfunction "3_3") (pintype "passive"))
      (node (ref "R10") (pin "1") (pinfunction "1_1") (pintype "passive"))
      (node (ref "R5") (pin "1") (pinfunction "1_1") (pintype "passive"))
    )
    (net (code "49") (name "unconnected-(S4-Pad1)") (class "Default")
      (node (ref "S4") (pin "1") (pinfunction "1_1") (pintype "passive"))
    )
    (net (code "50") (name "unconnected-(U1-ID-Pad4)") (class "Default")
      (node (ref "U1") (pin "4") (pinfunction "ID_4") (pintype "passive"))
    )
    (net (code "51") (name "unconnected-(U2-CTS#-Pad9)") (class "Default")
      (node (ref "U2") (pin "9") (pinfunction "CTS#_9") (pintype "passive"))
    )
    (net (code "52") (name "unconnected-(U2-DCD#-Pad12)") (class "Default")
      (node (ref "U2") (pin "12") (pinfunction "DCD#_12") (pintype "passive"))
    )
    (net (code "53") (name "unconnected-(U2-DSR#-Pad10)") (class "Default")
      (node (ref "U2") (pin "10") (pinfunction "DSR#_10") (pintype "passive"))
    )
    (net (code "54") (name "unconnected-(U2-DTR#-Pad13)") (class "Default")
      (node (ref "U2") (pin "13") (pinfunction "DTR#_13") (pintype "passive"))
    )
    (net (code "55") (name "unconnected-(U2-R232-Pad15)") (class "Default")
      (node (ref "U2") (pin "15") (pinfunction "R232_15") (pintype "passive"))
    )
    (net (code "56") (name "unconnected-(U2-RI#-Pad11)") (class "Default")
      (node (ref "U2") (pin "11") (pinfunction "RI#_11") (pintype "passive"))
    )
    (net (code "57") (name "unconnected-(U2-RTS#-Pad14)") (class "Default")
      (node (ref "U2") (pin "14") (pinfunction "RTS#_14") (pintype "passive"))
    )
    (net (code "58") (name "unconnected-(U8-ADO-Pad7)") (class "Default")
      (node (ref "U8") (pin "7") (pinfunction "ADO_7") (pintype "passive"))
    )
    (net (code "59") (name "unconnected-(U8-INT-Pad8)") (class "Default")
      (node (ref "U8") (pin "8") (pinfunction "INT_8") (pintype "passive"))
    )
    (net (code "60") (name "unconnected-(U8-XCL-Pad6)") (class "Default")
      (node (ref "U8") (pin "6") (pinfunction "XCL_6") (pintype "passive"))
    )
    (net (code "61") (name "unconnected-(U8-XDA-Pad5)") (class "Default")
      (node (ref "U8") (pin "5") (pinfunction "XDA_5") (pintype "passive"))
    )
  )
)
